# Sheet1.net
KiCad netlist of a schematic drawn in Altium Designer
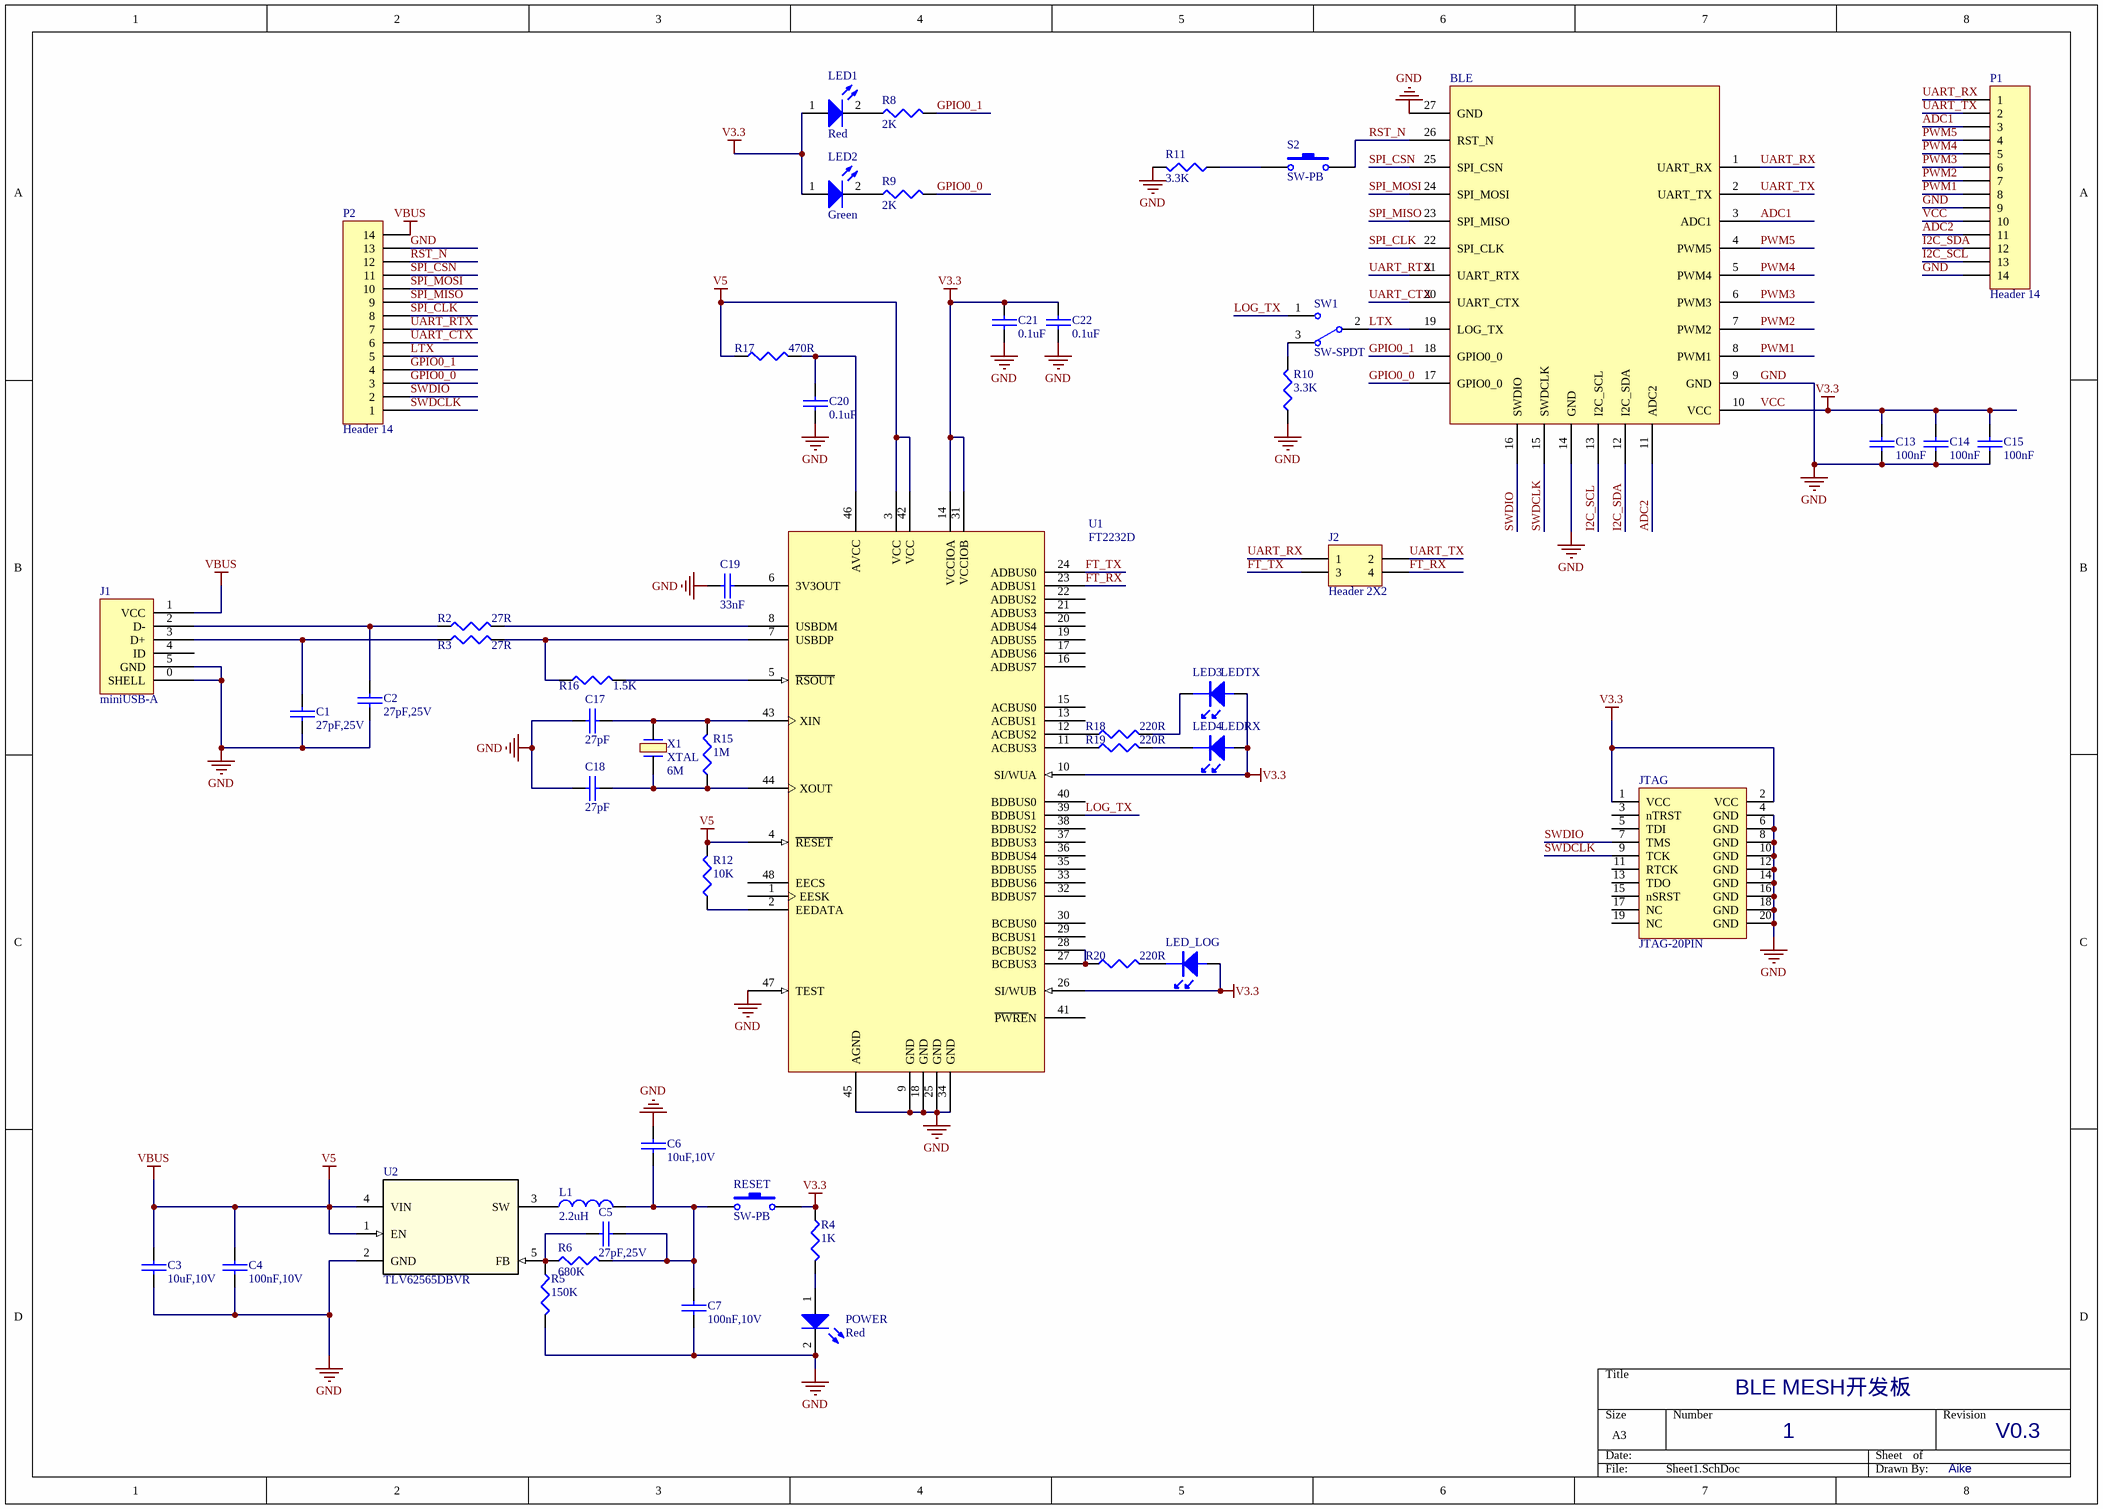
[diagram p0: Sheet1.SchDoc]

(export (version "E")
  (design (tool "Eeschema 10.0.6"))
  (components
    (comp (ref "BLE") (value "BLE") (footprint "BLE") (libsource (lib "my") (part "BLE")))
    (comp (ref "C1")
      (value "27pF,25V")
      (footprint "0603P")
      (description "Capacitor")
      (libsource (lib "my") (part "CAP"))
    )
    (comp (ref "C2")
      (value "27pF,25V")
      (footprint "0603P")
      (description "Capacitor")
      (libsource (lib "my") (part "CAP"))
    )
    (comp (ref "C3")
      (value "10uF,10V")
      (footprint "0603P")
      (description "Capacitor")
      (libsource (lib "my") (part "CAP"))
    )
    (comp (ref "C4")
      (value "100nF,10V")
      (footprint "0603P")
      (description "Capacitor")
      (libsource (lib "my") (part "CAP"))
    )
    (comp (ref "C5")
      (value "27pF,25V")
      (footprint "0603P")
      (description "Capacitor")
      (libsource (lib "my") (part "CAP"))
    )
    (comp (ref "C6")
      (value "10uF,10V")
      (footprint "0603P")
      (description "Capacitor")
      (libsource (lib "my") (part "CAP"))
    )
    (comp (ref "C7")
      (value "100nF,10V")
      (footprint "0603P")
      (description "Capacitor")
      (libsource (lib "my") (part "CAP"))
    )
    (comp (ref "C13")
      (value "100nF")
      (footprint "0603P")
      (description "Capacitor")
      (libsource (lib "my") (part "CAP"))
    )
    (comp (ref "C14")
      (value "100nF")
      (footprint "0603P")
      (description "Capacitor")
      (libsource (lib "my") (part "CAP"))
    )
    (comp (ref "C15")
      (value "100nF")
      (footprint "0603P")
      (description "Capacitor")
      (libsource (lib "my") (part "CAP"))
    )
    (comp (ref "C17")
      (value "27pF")
      (footprint "0603P")
      (description "Capacitor")
      (libsource (lib "my") (part "CAP"))
    )
    (comp (ref "C18")
      (value "27pF")
      (footprint "0603P")
      (description "Capacitor")
      (libsource (lib "my") (part "CAP"))
    )
    (comp (ref "C19")
      (value "33nF")
      (footprint "0603P")
      (description "Capacitor")
      (libsource (lib "my") (part "CAP"))
    )
    (comp (ref "C20")
      (value "0.1uF")
      (footprint "0603P")
      (description "Capacitor")
      (libsource (lib "my") (part "CAP"))
    )
    (comp (ref "C21")
      (value "0.1uF")
      (footprint "0603P")
      (description "Capacitor")
      (libsource (lib "my") (part "CAP"))
    )
    (comp (ref "C22")
      (value "0.1uF")
      (footprint "0603P")
      (description "Capacitor")
      (libsource (lib "my") (part "CAP"))
    )
    (comp (ref "J1")
      (value "miniUSB-A")
      (footprint "USB-min")
      (description "miniUSB-A  interface")
      (libsource (lib "my") (part "miniUSB-A"))
    )
    (comp (ref "J2")
      (value "Header 2X2")
      (footprint "HDR2X2")
      (description "Header, 2-Pin, Dual row")
      (fields (field (name "PUBLISHER") "Altium Limited"))
      (libsource (lib "Miscellaneous Connectors") (part "Header 2X2"))
    )
    (comp (ref "JTAG")
      (value "JTAG-20PIN")
      (footprint "IDC20_JTAG")
      (description "ARM_JTAG-20PIN")
      (libsource (lib "my") (part "ARM_JTAG"))
    )
    (comp (ref "L1")
      (value "2.2uH")
      (footprint "Inductor")
      (description "Inductor")
      (fields (field (name "PUBLISHER") "Altium Limited"))
      (libsource (lib "my") (part "Inductor"))
    )
    (comp (ref "LED1")
      (value "Red")
      (footprint "D0603")
      (description "Typical RED, GREEN, YELLOW, AMBER GaAs LED")
      (fields (field (name "PUBLISHER") "Altium Limited"))
      (libsource (lib "my") (part "LED2"))
    )
    (comp (ref "LED2")
      (value "Green")
      (footprint "D0603")
      (description "Typical RED, GREEN, YELLOW, AMBER GaAs LED")
      (fields (field (name "PUBLISHER") "Altium Limited"))
      (libsource (lib "my") (part "LED2"))
    )
    (comp (ref "LED3") (value "LEDTX") (footprint "LED_0603") (libsource (lib "FDD2322D") (part "LED")))
    (comp (ref "LED4") (value "LEDRX") (footprint "LED_0603") (libsource (lib "FDD2322D") (part "LED")))
    (comp (ref "LED_LOG") (value "LEDLOG") (footprint "LED_0603") (libsource (lib "FDD2322D") (part "LED")))
    (comp (ref "P1")
      (value "Header 14")
      (footprint "HDR1X14")
      (description "Header, 14-Pin")
      (fields (field (name "PUBLISHER") "Altium Limited"))
      (libsource (lib "Miscellaneous Connectors") (part "Header 14"))
    )
    (comp (ref "P2")
      (value "Header 14")
      (footprint "HDR1X14")
      (description "Header, 14-Pin")
      (fields (field (name "PUBLISHER") "Altium Limited"))
      (libsource (lib "") (part "Header 14_1"))
    )
    (comp (ref "POWER")
      (value "Red")
      (footprint "D0603")
      (description "Typical RED, GREEN, YELLOW, AMBER GaAs LED")
      (fields (field (name "PUBLISHER") "Altium Limited"))
      (libsource (lib "my") (part "LED2"))
    )
    (comp (ref "R2") (value "27R") (footprint "0603P") (libsource (lib "my") (part "R")))
    (comp (ref "R3") (value "27R") (footprint "0603P") (libsource (lib "my") (part "R")))
    (comp (ref "R4") (value "1K") (footprint "0603P") (libsource (lib "my") (part "R")))
    (comp (ref "R5") (value "150K") (footprint "0603P") (libsource (lib "my") (part "R")))
    (comp (ref "R6") (value "680K") (footprint "0603P") (libsource (lib "my") (part "R")))
    (comp (ref "R8") (value "2K") (footprint "0603P") (libsource (lib "my") (part "R")))
    (comp (ref "R9") (value "2K") (footprint "0603P") (libsource (lib "my") (part "R")))
    (comp (ref "R10") (value "3.3K") (footprint "0603P") (libsource (lib "my") (part "R")))
    (comp (ref "R11") (value "3.3K") (footprint "0603P") (libsource (lib "my") (part "R")))
    (comp (ref "R12") (value "10K") (footprint "0603P") (libsource (lib "my") (part "R")))
    (comp (ref "R15") (value "1M") (footprint "0603P") (libsource (lib "my") (part "R")))
    (comp (ref "R16") (value "1.5K") (footprint "0603P") (libsource (lib "my") (part "R")))
    (comp (ref "R17") (value "470R") (footprint "0603P") (libsource (lib "my") (part "R")))
    (comp (ref "R18") (value "220R") (footprint "0603P") (libsource (lib "my") (part "R")))
    (comp (ref "R19") (value "220R") (footprint "0603P") (libsource (lib "my") (part "R")))
    (comp (ref "R20") (value "220R") (footprint "0603P") (libsource (lib "my") (part "R")))
    (comp (ref "RESET")
      (value "SW-PB")
      (footprint "buttom_sp")
      (description "Switch")
      (fields (field (name "PUBLISHER") "Altium Limited"))
      (libsource (lib "my") (part "SW-PB"))
    )
    (comp (ref "S2")
      (value "SW-PB")
      (footprint "buttom_sp")
      (description "Switch")
      (fields (field (name "PUBLISHER") "Altium Limited"))
      (libsource (lib "my") (part "SW-PB"))
    )
    (comp (ref "SW1")
      (value "SW-SPDT")
      (footprint "SIP3")
      (description "SPDT Subminiature Toggle Switch, Right Angle Mounting, Vertical Actuation")
      (fields (field (name "PUBLISHER") "Altium Limited"))
      (libsource (lib "my") (part "SW-SPDT"))
    )
    (comp (ref "U1") (value "FT2232D") (footprint "TQFN48") (libsource (lib "FDD2322D") (part "FD2232D")))
    (comp (ref "U2")
      (value "TLV62565DBVR")
      (footprint "DBV0005A")
      (description "Imported")
      (fields
        (field (name "PARTNUMBER") "TLV62565DBV")
        (field (name "MANUFACTURER") "Texas Instruments")
        (field (name "MODIFIEDDATE") "Not shown in title block")
        (field (name "APPROVEDBY") "Not shown in title block")
        (field (name "CHECKEDBY") "Not shown in title block")
        (field (name "AUTHOR") "Not shown in title block")
        (field (name "ENGINEER") "Not shown in title block")
        (field (name "SYMBOLCREATOR") "a0411947")
        (field (name "PUBLISHER") "Texas Instruments")
      )
      (libsource (lib "2019-07-19_16-34-16") (part "TLV62565DBVR"))
    )
    (comp (ref "X1")
      (value "XTAL")
      (footprint "XTAL")
      (fields (field (name "ALTIUM_UNNAMED_1") "6M"))
      (libsource (lib "FDD2322D") (part "XTAL"))
    )
  )
  (nets
    (net (code "1") (name "/ADC1") (class "Default")
      (node (ref "BLE") (pin "3") (pinfunction "ADC1_3") (pintype "passive"))
      (node (ref "P1") (pin "3") (pinfunction "3_3") (pintype "passive"))
    )
    (net (code "2") (name "/ADC2") (class "Default")
      (node (ref "BLE") (pin "11") (pinfunction "ADC2_11") (pintype "passive"))
      (node (ref "P1") (pin "11") (pinfunction "11_11") (pintype "passive"))
    )
    (net (code "3") (name "/FT_RX") (class "Default")
      (node (ref "J2") (pin "4") (pinfunction "4_4") (pintype "passive"))
      (node (ref "U1") (pin "23") (pinfunction "ADBUS1_23") (pintype "passive"))
    )
    (net (code "4") (name "/FT_TX") (class "Default")
      (node (ref "J2") (pin "3") (pinfunction "3_3") (pintype "passive"))
      (node (ref "U1") (pin "24") (pinfunction "ADBUS0_24") (pintype "passive"))
    )
    (net (code "5") (name "/GPIO0_0") (class "Default")
      (node (ref "BLE") (pin "17") (pinfunction "GPIO0_0_17") (pintype "passive"))
      (node (ref "P2") (pin "3") (pinfunction "3_3") (pintype "passive"))
      (node (ref "R9") (pin "2") (pinfunction "2_2") (pintype "passive"))
    )
    (net (code "6") (name "/GPIO0_1") (class "Default")
      (node (ref "BLE") (pin "18") (pinfunction "GPIO0_0_18") (pintype "passive"))
      (node (ref "P2") (pin "4") (pinfunction "4_4") (pintype "passive"))
      (node (ref "R8") (pin "2") (pinfunction "2_2") (pintype "passive"))
    )
    (net (code "7") (name "/I2C_SCL") (class "Default")
      (node (ref "BLE") (pin "13") (pinfunction "I2C_SCL_13") (pintype "passive"))
      (node (ref "P1") (pin "13") (pinfunction "13_13") (pintype "passive"))
    )
    (net (code "8") (name "/I2C_SDA") (class "Default")
      (node (ref "BLE") (pin "12") (pinfunction "I2C_SDA_12") (pintype "passive"))
      (node (ref "P1") (pin "12") (pinfunction "12_12") (pintype "passive"))
    )
    (net (code "9") (name "/LOG_TX") (class "Default")
      (node (ref "SW1") (pin "1") (pintype "passive"))
      (node (ref "U1") (pin "39") (pinfunction "BDBUS1_39") (pintype "passive"))
    )
    (net (code "10") (name "/LTX") (class "Default")
      (node (ref "BLE") (pin "19") (pinfunction "LOG_TX_19") (pintype "passive"))
      (node (ref "P2") (pin "5") (pinfunction "5_5") (pintype "passive"))
      (node (ref "SW1") (pin "2") (pintype "passive"))
    )
    (net (code "11") (name "/PWM1") (class "Default")
      (node (ref "BLE") (pin "8") (pinfunction "PWM1_8") (pintype "passive"))
      (node (ref "P1") (pin "8") (pinfunction "8_8") (pintype "passive"))
    )
    (net (code "12") (name "/PWM2") (class "Default")
      (node (ref "BLE") (pin "7") (pinfunction "PWM2_7") (pintype "passive"))
      (node (ref "P1") (pin "7") (pinfunction "7_7") (pintype "passive"))
    )
    (net (code "13") (name "/PWM3") (class "Default")
      (node (ref "BLE") (pin "6") (pinfunction "PWM3_6") (pintype "passive"))
      (node (ref "P1") (pin "6") (pinfunction "6_6") (pintype "passive"))
    )
    (net (code "14") (name "/PWM4") (class "Default")
      (node (ref "BLE") (pin "5") (pinfunction "PWM4_5") (pintype "passive"))
      (node (ref "P1") (pin "5") (pinfunction "5_5") (pintype "passive"))
    )
    (net (code "15") (name "/PWM5") (class "Default")
      (node (ref "BLE") (pin "4") (pinfunction "PWM5_4") (pintype "passive"))
      (node (ref "P1") (pin "4") (pinfunction "4_4") (pintype "passive"))
    )
    (net (code "16") (name "/RST_N") (class "Default")
      (node (ref "BLE") (pin "26") (pinfunction "RST_N_26") (pintype "passive"))
      (node (ref "P2") (pin "12") (pinfunction "12_12") (pintype "passive"))
      (node (ref "S2") (pin "2") (pinfunction "2_2") (pintype "passive"))
    )
    (net (code "17") (name "/SPI_CLK") (class "Default")
      (node (ref "BLE") (pin "22") (pinfunction "SPI_CLK_22") (pintype "passive"))
      (node (ref "P2") (pin "8") (pinfunction "8_8") (pintype "passive"))
    )
    (net (code "18") (name "/SPI_CSN") (class "Default")
      (node (ref "BLE") (pin "25") (pinfunction "SPI_CSN_25") (pintype "passive"))
      (node (ref "P2") (pin "11") (pinfunction "11_11") (pintype "passive"))
    )
    (net (code "19") (name "/SPI_MISO") (class "Default")
      (node (ref "BLE") (pin "23") (pinfunction "SPI_MISO_23") (pintype "passive"))
      (node (ref "P2") (pin "9") (pinfunction "9_9") (pintype "passive"))
    )
    (net (code "20") (name "/SPI_MOSI") (class "Default")
      (node (ref "BLE") (pin "24") (pinfunction "SPI_MOSI_24") (pintype "passive"))
      (node (ref "P2") (pin "10") (pinfunction "10_10") (pintype "passive"))
    )
    (net (code "21") (name "/SWDCLK") (class "Default")
      (node (ref "BLE") (pin "15") (pinfunction "SWDCLK_15") (pintype "passive"))
      (node (ref "JTAG") (pin "9") (pinfunction "TCK_9") (pintype "passive"))
      (node (ref "P2") (pin "1") (pinfunction "1_1") (pintype "passive"))
    )
    (net (code "22") (name "/SWDIO") (class "Default")
      (node (ref "BLE") (pin "16") (pinfunction "SWDIO_16") (pintype "passive"))
      (node (ref "JTAG") (pin "7") (pinfunction "TMS_7") (pintype "passive"))
      (node (ref "P2") (pin "2") (pinfunction "2_2") (pintype "passive"))
    )
    (net (code "23") (name "/UART_CTX") (class "Default")
      (node (ref "BLE") (pin "20") (pinfunction "UART_CTX_20") (pintype "passive"))
      (node (ref "P2") (pin "6") (pinfunction "6_6") (pintype "passive"))
    )
    (net (code "24") (name "/UART_RTX") (class "Default")
      (node (ref "BLE") (pin "21") (pinfunction "UART_RTX_21") (pintype "passive"))
      (node (ref "P2") (pin "7") (pinfunction "7_7") (pintype "passive"))
    )
    (net (code "25") (name "/UART_RX") (class "Default")
      (node (ref "BLE") (pin "1") (pinfunction "UART_RX_1") (pintype "passive"))
      (node (ref "J2") (pin "1") (pinfunction "1_1") (pintype "passive"))
      (node (ref "P1") (pin "1") (pinfunction "1_1") (pintype "passive"))
    )
    (net (code "26") (name "/UART_TX") (class "Default")
      (node (ref "BLE") (pin "2") (pinfunction "UART_TX_2") (pintype "passive"))
      (node (ref "J2") (pin "2") (pinfunction "2_2") (pintype "passive"))
      (node (ref "P1") (pin "2") (pinfunction "2_2") (pintype "passive"))
    )
    (net (code "27") (name "GND") (class "Default")
      (node (ref "BLE") (pin "14") (pinfunction "GND_14") (pintype "passive"))
      (node (ref "BLE") (pin "27") (pinfunction "GND_27") (pintype "passive"))
      (node (ref "BLE") (pin "9") (pinfunction "GND_9") (pintype "passive"))
      (node (ref "C1") (pin "1") (pinfunction "1_1") (pintype "passive"))
      (node (ref "C13") (pin "2") (pinfunction "2_2") (pintype "passive"))
      (node (ref "C14") (pin "2") (pinfunction "2_2") (pintype "passive"))
      (node (ref "C15") (pin "2") (pinfunction "2_2") (pintype "passive"))
      (node (ref "C17") (pin "2") (pinfunction "2_2") (pintype "passive"))
      (node (ref "C18") (pin "2") (pinfunction "2_2") (pintype "passive"))
      (node (ref "C19") (pin "2") (pinfunction "2_2") (pintype "passive"))
      (node (ref "C2") (pin "1") (pinfunction "1_1") (pintype "passive"))
      (node (ref "C20") (pin "1") (pinfunction "1_1") (pintype "passive"))
      (node (ref "C21") (pin "1") (pinfunction "1_1") (pintype "passive"))
      (node (ref "C22") (pin "1") (pinfunction "1_1") (pintype "passive"))
      (node (ref "C3") (pin "2") (pinfunction "2_2") (pintype "passive"))
      (node (ref "C4") (pin "2") (pinfunction "2_2") (pintype "passive"))
      (node (ref "C6") (pin "1") (pinfunction "1_1") (pintype "passive"))
      (node (ref "C7") (pin "2") (pinfunction "2_2") (pintype "passive"))
      (node (ref "J1") (pin "0") (pinfunction "SHELL_0") (pintype "passive"))
      (node (ref "J1") (pin "5") (pinfunction "GND_5") (pintype "passive"))
      (node (ref "JTAG") (pin "10") (pinfunction "GND_10") (pintype "passive"))
      (node (ref "JTAG") (pin "12") (pinfunction "GND_12") (pintype "passive"))
      (node (ref "JTAG") (pin "14") (pinfunction "GND_14") (pintype "passive"))
      (node (ref "JTAG") (pin "16") (pinfunction "GND_16") (pintype "passive"))
      (node (ref "JTAG") (pin "18") (pinfunction "GND_18") (pintype "passive"))
      (node (ref "JTAG") (pin "20") (pinfunction "GND_20") (pintype "passive"))
      (node (ref "JTAG") (pin "4") (pinfunction "GND_4") (pintype "passive"))
      (node (ref "JTAG") (pin "6") (pinfunction "GND_6") (pintype "passive"))
      (node (ref "JTAG") (pin "8") (pinfunction "GND_8") (pintype "passive"))
      (node (ref "P1") (pin "14") (pinfunction "14_14") (pintype "passive"))
      (node (ref "P1") (pin "9") (pinfunction "9_9") (pintype "passive"))
      (node (ref "P2") (pin "13") (pinfunction "13_13") (pintype "passive"))
      (node (ref "POWER") (pin "2") (pinfunction "K_2") (pintype "passive"))
      (node (ref "R10") (pin "1") (pinfunction "1_1") (pintype "passive"))
      (node (ref "R11") (pin "2") (pinfunction "2_2") (pintype "passive"))
      (node (ref "R5") (pin "2") (pinfunction "2_2") (pintype "passive"))
      (node (ref "U1") (pin "18") (pinfunction "GND_18") (pintype "passive"))
      (node (ref "U1") (pin "25") (pinfunction "GND_25") (pintype "power_in"))
      (node (ref "U1") (pin "34") (pinfunction "GND_34") (pintype "power_in"))
      (node (ref "U1") (pin "45") (pinfunction "AGND_45") (pintype "power_in"))
      (node (ref "U1") (pin "47") (pinfunction "TEST_47") (pintype "input"))
      (node (ref "U1") (pin "9") (pinfunction "GND_9") (pintype "power_in"))
      (node (ref "U2") (pin "2") (pinfunction "GND_2") (pintype "power_in"))
    )
    (net (code "28") (name "Net-(C5-Pad2)") (class "Default")
      (node (ref "C5") (pin "2") (pinfunction "2_2") (pintype "passive"))
      (node (ref "C6") (pin "2") (pinfunction "2_2") (pintype "passive"))
      (node (ref "C7") (pin "1") (pinfunction "1_1") (pintype "passive"))
      (node (ref "L1") (pin "2") (pinfunction "2_2") (pintype "passive"))
      (node (ref "R6") (pin "2") (pinfunction "2_2") (pintype "passive"))
      (node (ref "RESET") (pin "1") (pinfunction "1_1") (pintype "passive"))
    )
    (net (code "29") (name "Net-(J1-D+)") (class "Default")
      (node (ref "C1") (pin "2") (pinfunction "2_2") (pintype "passive"))
      (node (ref "J1") (pin "3") (pinfunction "D+_3") (pintype "passive"))
      (node (ref "R3") (pin "1") (pinfunction "1_1") (pintype "passive"))
    )
    (net (code "30") (name "Net-(J1-D-)") (class "Default")
      (node (ref "C2") (pin "2") (pinfunction "2_2") (pintype "passive"))
      (node (ref "J1") (pin "2") (pinfunction "D-_2") (pintype "passive"))
      (node (ref "R2") (pin "1") (pinfunction "1_1") (pintype "passive"))
    )
    (net (code "31") (name "Net-(LED1-K)") (class "Default")
      (node (ref "LED1") (pin "2") (pinfunction "K_2") (pintype "passive"))
      (node (ref "R8") (pin "1") (pinfunction "1_1") (pintype "passive"))
    )
    (net (code "32") (name "Net-(LED2-K)") (class "Default")
      (node (ref "LED2") (pin "2") (pinfunction "K_2") (pintype "passive"))
      (node (ref "R9") (pin "1") (pinfunction "1_1") (pintype "passive"))
    )
    (net (code "33") (name "Net-(LED3-Pad2)") (class "Default")
      (node (ref "LED3") (pin "2") (pintype "passive"))
      (node (ref "R18") (pin "2") (pinfunction "2_2") (pintype "passive"))
    )
    (net (code "34") (name "Net-(LED4-Pad2)") (class "Default")
      (node (ref "LED4") (pin "2") (pintype "passive"))
      (node (ref "R19") (pin "2") (pinfunction "2_2") (pintype "passive"))
    )
    (net (code "35") (name "Net-(LED_LOG-Pad2)") (class "Default")
      (node (ref "LED_LOG") (pin "2") (pintype "passive"))
      (node (ref "R20") (pin "2") (pinfunction "2_2") (pintype "passive"))
    )
    (net (code "36") (name "Net-(POWER-A)") (class "Default")
      (node (ref "POWER") (pin "1") (pinfunction "A_1") (pintype "passive"))
      (node (ref "R4") (pin "2") (pinfunction "2_2") (pintype "passive"))
    )
    (net (code "37") (name "Net-(R10-Pad2)") (class "Default")
      (node (ref "R10") (pin "2") (pinfunction "2_2") (pintype "passive"))
      (node (ref "SW1") (pin "3") (pintype "passive"))
    )
    (net (code "38") (name "Net-(R11-Pad1)") (class "Default")
      (node (ref "R11") (pin "1") (pinfunction "1_1") (pintype "passive"))
      (node (ref "S2") (pin "1") (pinfunction "1_1") (pintype "passive"))
    )
    (net (code "39") (name "Net-(U1-3V3OUT)") (class "Default")
      (node (ref "C19") (pin "1") (pinfunction "1_1") (pintype "passive"))
      (node (ref "U1") (pin "6") (pinfunction "3V3OUT_6") (pintype "power_in"))
    )
    (net (code "40") (name "Net-(U1-ACBUS2)") (class "Default")
      (node (ref "R18") (pin "1") (pinfunction "1_1") (pintype "passive"))
      (node (ref "U1") (pin "12") (pinfunction "ACBUS2_12") (pintype "passive"))
    )
    (net (code "41") (name "Net-(U1-ACBUS3)") (class "Default")
      (node (ref "R19") (pin "1") (pinfunction "1_1") (pintype "passive"))
      (node (ref "U1") (pin "11") (pinfunction "ACBUS3_11") (pintype "passive"))
    )
    (net (code "42") (name "Net-(U1-AVCC)") (class "Default")
      (node (ref "C20") (pin "2") (pinfunction "2_2") (pintype "passive"))
      (node (ref "R17") (pin "2") (pinfunction "2_2") (pintype "passive"))
      (node (ref "U1") (pin "46") (pinfunction "AVCC_46") (pintype "power_in"))
    )
    (net (code "43") (name "Net-(U1-BCBUS2)") (class "Default")
      (node (ref "R20") (pin "1") (pinfunction "1_1") (pintype "passive"))
      (node (ref "U1") (pin "27") (pinfunction "BCBUS3_27") (pintype "passive"))
      (node (ref "U1") (pin "28") (pinfunction "BCBUS2_28") (pintype "passive"))
    )
    (net (code "44") (name "Net-(U1-EEDATA)") (class "Default")
      (node (ref "R12") (pin "1") (pinfunction "1_1") (pintype "passive"))
      (node (ref "U1") (pin "2") (pinfunction "EEDATA_2") (pintype "passive"))
    )
    (net (code "45") (name "Net-(U1-USBDM)") (class "Default")
      (node (ref "R2") (pin "2") (pinfunction "2_2") (pintype "passive"))
      (node (ref "U1") (pin "8") (pinfunction "USBDM_8") (pintype "passive"))
    )
    (net (code "46") (name "Net-(U1-USBDP)") (class "Default")
      (node (ref "R16") (pin "1") (pinfunction "1_1") (pintype "passive"))
      (node (ref "R3") (pin "2") (pinfunction "2_2") (pintype "passive"))
      (node (ref "U1") (pin "7") (pinfunction "USBDP_7") (pintype "passive"))
    )
    (net (code "47") (name "Net-(U1-XIN)") (class "Default")
      (node (ref "C17") (pin "1") (pinfunction "1_1") (pintype "passive"))
      (node (ref "R15") (pin "2") (pinfunction "2_2") (pintype "passive"))
      (node (ref "U1") (pin "43") (pinfunction "XIN_43") (pintype "passive"))
      (node (ref "X1") (pin "2") (pinfunction "2_2") (pintype "passive"))
    )
    (net (code "48") (name "Net-(U1-XOUT)") (class "Default")
      (node (ref "C18") (pin "1") (pinfunction "1_1") (pintype "passive"))
      (node (ref "R15") (pin "1") (pinfunction "1_1") (pintype "passive"))
      (node (ref "U1") (pin "44") (pinfunction "XOUT_44") (pintype "passive"))
      (node (ref "X1") (pin "1") (pinfunction "1_1") (pintype "passive"))
    )
    (net (code "49") (name "Net-(U1-~{RSOUT})") (class "Default")
      (node (ref "R16") (pin "2") (pinfunction "2_2") (pintype "passive"))
      (node (ref "U1") (pin "5") (pinfunction "~{RSOUT}_5") (pintype "input"))
    )
    (net (code "50") (name "Net-(U2-FB)") (class "Default")
      (node (ref "C5") (pin "1") (pinfunction "1_1") (pintype "passive"))
      (node (ref "R5") (pin "1") (pinfunction "1_1") (pintype "passive"))
      (node (ref "R6") (pin "1") (pinfunction "1_1") (pintype "passive"))
      (node (ref "U2") (pin "5") (pinfunction "FB_5") (pintype "input"))
    )
    (net (code "51") (name "Net-(U2-SW)") (class "Default")
      (node (ref "L1") (pin "1") (pinfunction "1_1") (pintype "passive"))
      (node (ref "U2") (pin "3") (pinfunction "SW_3") (pintype "power_in"))
    )
    (net (code "52") (name "V3.3") (class "Default")
      (node (ref "BLE") (pin "10") (pinfunction "VCC_10") (pintype "passive"))
      (node (ref "C13") (pin "1") (pinfunction "1_1") (pintype "passive"))
      (node (ref "C14") (pin "1") (pinfunction "1_1") (pintype "passive"))
      (node (ref "C15") (pin "1") (pinfunction "1_1") (pintype "passive"))
      (node (ref "C21") (pin "2") (pinfunction "2_2") (pintype "passive"))
      (node (ref "C22") (pin "2") (pinfunction "2_2") (pintype "passive"))
      (node (ref "JTAG") (pin "1") (pinfunction "VCC_1") (pintype "passive"))
      (node (ref "JTAG") (pin "2") (pinfunction "VCC_2") (pintype "passive"))
      (node (ref "LED1") (pin "1") (pinfunction "A_1") (pintype "passive"))
      (node (ref "LED2") (pin "1") (pinfunction "A_1") (pintype "passive"))
      (node (ref "LED3") (pin "1") (pintype "passive"))
      (node (ref "LED4") (pin "1") (pintype "passive"))
      (node (ref "LED_LOG") (pin "1") (pintype "passive"))
      (node (ref "P1") (pin "10") (pinfunction "10_10") (pintype "passive"))
      (node (ref "R4") (pin "1") (pinfunction "1_1") (pintype "passive"))
      (node (ref "RESET") (pin "2") (pinfunction "2_2") (pintype "passive"))
      (node (ref "U1") (pin "10") (pinfunction "SI/WUA_10") (pintype "input"))
      (node (ref "U1") (pin "14") (pinfunction "VCCIOA_14") (pintype "passive"))
      (node (ref "U1") (pin "26") (pinfunction "SI/WUB_26") (pintype "input"))
      (node (ref "U1") (pin "31") (pinfunction "VCCIOB_31") (pintype "passive"))
    )
    (net (code "53") (name "V5") (class "Default")
      (node (ref "C3") (pin "1") (pinfunction "1_1") (pintype "passive"))
      (node (ref "C4") (pin "1") (pinfunction "1_1") (pintype "passive"))
      (node (ref "J1") (pin "1") (pinfunction "VCC_1") (pintype "passive"))
      (node (ref "P2") (pin "14") (pinfunction "14_14") (pintype "passive"))
      (node (ref "R12") (pin "2") (pinfunction "2_2") (pintype "passive"))
      (node (ref "R17") (pin "1") (pinfunction "1_1") (pintype "passive"))
      (node (ref "U1") (pin "3") (pinfunction "VCC_3") (pintype "power_in"))
      (node (ref "U1") (pin "4") (pinfunction "~{RESET}_4") (pintype "input"))
      (node (ref "U1") (pin "42") (pinfunction "VCC_42") (pintype "power_in"))
      (node (ref "U2") (pin "1") (pinfunction "EN_1") (pintype "input"))
      (node (ref "U2") (pin "4") (pinfunction "VIN_4") (pintype "power_in"))
    )
    (net (code "54") (name "unconnected-(J1-ID-Pad4)") (class "Default")
      (node (ref "J1") (pin "4") (pinfunction "ID_4") (pintype "passive"))
    )
    (net (code "55") (name "unconnected-(JTAG-NC-Pad17)") (class "Default")
      (node (ref "JTAG") (pin "17") (pinfunction "NC_17") (pintype "passive"))
    )
    (net (code "56") (name "unconnected-(JTAG-NC-Pad19)") (class "Default")
      (node (ref "JTAG") (pin "19") (pinfunction "NC_19") (pintype "passive"))
    )
    (net (code "57") (name "unconnected-(JTAG-RTCK-Pad11)") (class "Default")
      (node (ref "JTAG") (pin "11") (pinfunction "RTCK_11") (pintype "passive"))
    )
    (net (code "58") (name "unconnected-(JTAG-TDI-Pad5)") (class "Default")
      (node (ref "JTAG") (pin "5") (pinfunction "TDI_5") (pintype "passive"))
    )
    (net (code "59") (name "unconnected-(JTAG-TDO-Pad13)") (class "Default")
      (node (ref "JTAG") (pin "13") (pinfunction "TDO_13") (pintype "passive"))
    )
    (net (code "60") (name "unconnected-(JTAG-nSRST-Pad15)") (class "Default")
      (node (ref "JTAG") (pin "15") (pinfunction "nSRST_15") (pintype "passive"))
    )
    (net (code "61") (name "unconnected-(JTAG-nTRST-Pad3)") (class "Default")
      (node (ref "JTAG") (pin "3") (pinfunction "nTRST_3") (pintype "passive"))
    )
    (net (code "62") (name "unconnected-(U1-ACBUS0-Pad15)") (class "Default")
      (node (ref "U1") (pin "15") (pinfunction "ACBUS0_15") (pintype "passive"))
    )
    (net (code "63") (name "unconnected-(U1-ACBUS1-Pad13)") (class "Default")
      (node (ref "U1") (pin "13") (pinfunction "ACBUS1_13") (pintype "passive"))
    )
    (net (code "64") (name "unconnected-(U1-ADBUS2-Pad22)") (class "Default")
      (node (ref "U1") (pin "22") (pinfunction "ADBUS2_22") (pintype "passive"))
    )
    (net (code "65") (name "unconnected-(U1-ADBUS3-Pad21)") (class "Default")
      (node (ref "U1") (pin "21") (pinfunction "ADBUS3_21") (pintype "passive"))
    )
    (net (code "66") (name "unconnected-(U1-ADBUS4-Pad20)") (class "Default")
      (node (ref "U1") (pin "20") (pinfunction "ADBUS4_20") (pintype "passive"))
    )
    (net (code "67") (name "unconnected-(U1-ADBUS5-Pad19)") (class "Default")
      (node (ref "U1") (pin "19") (pinfunction "ADBUS5_19") (pintype "passive"))
    )
    (net (code "68") (name "unconnected-(U1-ADBUS6-Pad17)") (class "Default")
      (node (ref "U1") (pin "17") (pinfunction "ADBUS6_17") (pintype "passive"))
    )
    (net (code "69") (name "unconnected-(U1-ADBUS7-Pad16)") (class "Default")
      (node (ref "U1") (pin "16") (pinfunction "ADBUS7_16") (pintype "passive"))
    )
    (net (code "70") (name "unconnected-(U1-BCBUS0-Pad30)") (class "Default")
      (node (ref "U1") (pin "30") (pinfunction "BCBUS0_30") (pintype "passive"))
    )
    (net (code "71") (name "unconnected-(U1-BCBUS1-Pad29)") (class "Default")
      (node (ref "U1") (pin "29") (pinfunction "BCBUS1_29") (pintype "passive"))
    )
    (net (code "72") (name "unconnected-(U1-BDBUS0-Pad40)") (class "Default")
      (node (ref "U1") (pin "40") (pinfunction "BDBUS0_40") (pintype "passive"))
    )
    (net (code "73") (name "unconnected-(U1-BDBUS2-Pad38)") (class "Default")
      (node (ref "U1") (pin "38") (pinfunction "BDBUS2_38") (pintype "passive"))
    )
    (net (code "74") (name "unconnected-(U1-BDBUS3-Pad37)") (class "Default")
      (node (ref "U1") (pin "37") (pinfunction "BDBUS3_37") (pintype "passive"))
    )
    (net (code "75") (name "unconnected-(U1-BDBUS4-Pad36)") (class "Default")
      (node (ref "U1") (pin "36") (pinfunction "BDBUS4_36") (pintype "passive"))
    )
    (net (code "76") (name "unconnected-(U1-BDBUS5-Pad35)") (class "Default")
      (node (ref "U1") (pin "35") (pinfunction "BDBUS5_35") (pintype "passive"))
    )
    (net (code "77") (name "unconnected-(U1-BDBUS6-Pad33)") (class "Default")
      (node (ref "U1") (pin "33") (pinfunction "BDBUS6_33") (pintype "passive"))
    )
    (net (code "78") (name "unconnected-(U1-BDBUS7-Pad32)") (class "Default")
      (node (ref "U1") (pin "32") (pinfunction "BDBUS7_32") (pintype "passive"))
    )
    (net (code "79") (name "unconnected-(U1-EECS-Pad48)") (class "Default")
      (node (ref "U1") (pin "48") (pinfunction "EECS_48") (pintype "passive"))
    )
    (net (code "80") (name "unconnected-(U1-EESK-Pad1)") (class "Default")
      (node (ref "U1") (pin "1") (pinfunction "EESK_1") (pintype "passive"))
    )
    (net (code "81") (name "unconnected-(U1-~{PWRE}N-Pad41)") (class "Default")
      (node (ref "U1") (pin "41") (pinfunction "~{PWRE}N_41") (pintype "passive"))
    )
  )
)
